# USB-HID-Control-Switches-Module.net
KiCad netlist of a schematic drawn in EAGLE
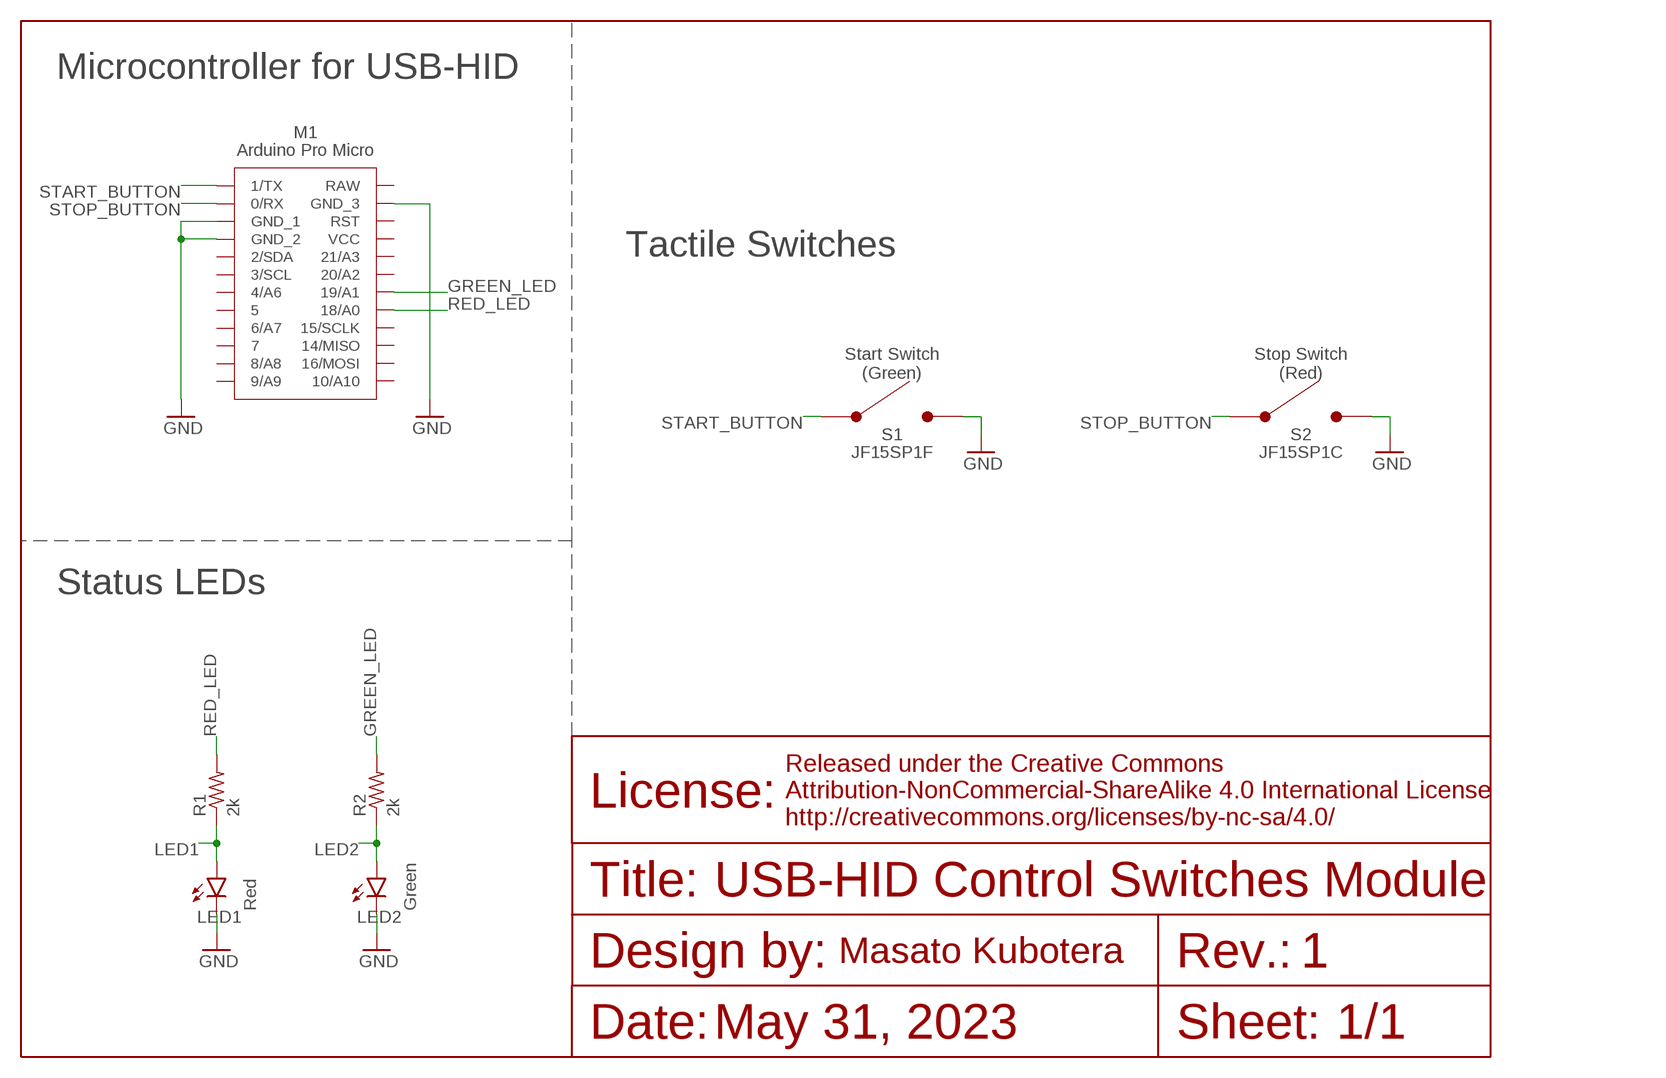
[diagram p0: schematic, sheet 1]

(export (version "E")
  (design (tool "Eeschema 10.0.6"))
  (components
    (comp (ref "LED1")
      (value "Red")
      (footprint "eagle-import:SML0603")
      (libsource (lib "eagle-import") (part "LEDSML0603"))
    )
    (comp (ref "LED2")
      (value "Green")
      (footprint "eagle-import:SML0603")
      (libsource (lib "eagle-import") (part "LEDSML0603"))
    )
    (comp (ref "M1")
      (value "PRO_MICRO_SMD")
      (footprint "eagle-import:PRO_MICRO_SMD")
      (libsource (lib "eagle-import") (part "PRO_MICRO_SMD"))
    )
    (comp (ref "R1")
      (value "2k")
      (footprint "eagle-import:R0603")
      (libsource (lib "eagle-import") (part "R-US_R0603"))
    )
    (comp (ref "R2")
      (value "2k")
      (footprint "eagle-import:R0603")
      (libsource (lib "eagle-import") (part "R-US_R0603"))
    )
    (comp (ref "S1")
      (value "JF15SP1F")
      (footprint "eagle-import:JF15SP1")
      (libsource (lib "eagle-import") (part "JF15SP1F"))
    )
    (comp (ref "S2")
      (value "JF15SP1C")
      (footprint "eagle-import:JF15SP1")
      (libsource (lib "eagle-import") (part "JF15SP1C"))
    )
  )
  (nets
    (net (code "1") (name "/GREEN_LED") (class "Default")
      (node (ref "M1") (pin "18") (pinfunction "19/A1_18") (pintype "bidirectional"))
      (node (ref "R2") (pin "2") (pinfunction "2_2") (pintype "passive"))
    )
    (net (code "2") (name "/LED1") (class "Default")
      (node (ref "LED1") (pin "A") (pinfunction "A_A") (pintype "passive"))
      (node (ref "R1") (pin "1") (pinfunction "1_1") (pintype "passive"))
    )
    (net (code "3") (name "/LED2") (class "Default")
      (node (ref "LED2") (pin "A") (pinfunction "A_A") (pintype "passive"))
      (node (ref "R2") (pin "1") (pinfunction "1_1") (pintype "passive"))
    )
    (net (code "4") (name "/RED_LED") (class "Default")
      (node (ref "M1") (pin "17") (pinfunction "18/A0_17") (pintype "bidirectional"))
      (node (ref "R1") (pin "2") (pinfunction "2_2") (pintype "passive"))
    )
    (net (code "5") (name "/START_BUTTON") (class "Default")
      (node (ref "M1") (pin "1") (pinfunction "1/TX_1") (pintype "bidirectional"))
      (node (ref "S1") (pin "1") (pinfunction "P$1_1") (pintype "bidirectional"))
      (node (ref "S1") (pin "2") (pinfunction "P$1_2") (pintype "bidirectional"))
    )
    (net (code "6") (name "/STOP_BUTTON") (class "Default")
      (node (ref "M1") (pin "2") (pinfunction "0/RX_2") (pintype "bidirectional"))
      (node (ref "S2") (pin "1") (pinfunction "P$1_1") (pintype "bidirectional"))
      (node (ref "S2") (pin "2") (pinfunction "P$1_2") (pintype "bidirectional"))
    )
    (net (code "7") (name "GND") (class "Default")
      (node (ref "LED1") (pin "C") (pinfunction "C_C") (pintype "passive"))
      (node (ref "LED2") (pin "C") (pinfunction "C_C") (pintype "passive"))
      (node (ref "M1") (pin "23") (pinfunction "GND_3_23") (pintype "bidirectional"))
      (node (ref "M1") (pin "3") (pinfunction "GND_1_3") (pintype "bidirectional"))
      (node (ref "M1") (pin "4") (pinfunction "GND_2_4") (pintype "bidirectional"))
      (node (ref "S1") (pin "3") (pinfunction "P$2_3") (pintype "bidirectional"))
      (node (ref "S1") (pin "4") (pinfunction "P$2_4") (pintype "bidirectional"))
      (node (ref "S2") (pin "3") (pinfunction "P$2_3") (pintype "bidirectional"))
      (node (ref "S2") (pin "4") (pinfunction "P$2_4") (pintype "bidirectional"))
    )
    (net (code "8") (name "unconnected-(M1-2{slash}SDA-Pad5)") (class "Default")
      (node (ref "M1") (pin "5") (pinfunction "2/SDA_5") (pintype "bidirectional"))
    )
    (net (code "9") (name "unconnected-(M1-3{slash}SCL-Pad6)") (class "Default")
      (node (ref "M1") (pin "6") (pinfunction "3/SCL_6") (pintype "bidirectional"))
    )
    (net (code "10") (name "unconnected-(M1-4{slash}A6-Pad7)") (class "Default")
      (node (ref "M1") (pin "7") (pinfunction "4/A6_7") (pintype "bidirectional"))
    )
    (net (code "11") (name "unconnected-(M1-5-Pad8)") (class "Default")
      (node (ref "M1") (pin "8") (pinfunction "5_8") (pintype "bidirectional"))
    )
    (net (code "12") (name "unconnected-(M1-6{slash}A7-Pad9)") (class "Default")
      (node (ref "M1") (pin "9") (pinfunction "6/A7_9") (pintype "bidirectional"))
    )
    (net (code "13") (name "unconnected-(M1-7-Pad10)") (class "Default")
      (node (ref "M1") (pin "10") (pinfunction "7_10") (pintype "bidirectional"))
    )
    (net (code "14") (name "unconnected-(M1-8{slash}A8-Pad11)") (class "Default")
      (node (ref "M1") (pin "11") (pinfunction "8/A8_11") (pintype "bidirectional"))
    )
    (net (code "15") (name "unconnected-(M1-9{slash}A9-Pad12)") (class "Default")
      (node (ref "M1") (pin "12") (pinfunction "9/A9_12") (pintype "bidirectional"))
    )
    (net (code "16") (name "unconnected-(M1-10{slash}A10-Pad13)") (class "Default")
      (node (ref "M1") (pin "13") (pinfunction "10/A10_13") (pintype "bidirectional"))
    )
    (net (code "17") (name "unconnected-(M1-14{slash}MISO-Pad15)") (class "Default")
      (node (ref "M1") (pin "15") (pinfunction "14/MISO_15") (pintype "bidirectional"))
    )
    (net (code "18") (name "unconnected-(M1-15{slash}SCLK-Pad16)") (class "Default")
      (node (ref "M1") (pin "16") (pinfunction "15/SCLK_16") (pintype "bidirectional"))
    )
    (net (code "19") (name "unconnected-(M1-16{slash}MOSI-Pad14)") (class "Default")
      (node (ref "M1") (pin "14") (pinfunction "16/MOSI_14") (pintype "bidirectional"))
    )
    (net (code "20") (name "unconnected-(M1-20{slash}A2-Pad19)") (class "Default")
      (node (ref "M1") (pin "19") (pinfunction "20/A2_19") (pintype "bidirectional"))
    )
    (net (code "21") (name "unconnected-(M1-21{slash}A3-Pad20)") (class "Default")
      (node (ref "M1") (pin "20") (pinfunction "21/A3_20") (pintype "bidirectional"))
    )
    (net (code "22") (name "unconnected-(M1-RAW-Pad24)") (class "Default")
      (node (ref "M1") (pin "24") (pinfunction "RAW_24") (pintype "bidirectional"))
    )
    (net (code "23") (name "unconnected-(M1-RST-Pad22)") (class "Default")
      (node (ref "M1") (pin "22") (pinfunction "RST_22") (pintype "bidirectional"))
    )
    (net (code "24") (name "unconnected-(M1-VCC-Pad21)") (class "Default")
      (node (ref "M1") (pin "21") (pinfunction "VCC_21") (pintype "bidirectional"))
    )
  )
)
